# touch_w_scroll.net
KiCad netlist of a schematic drawn in EAGLE
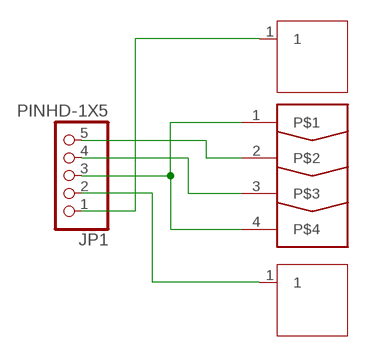
[diagram p0: schematic, sheet 1]

(export (version "E")
  (design (tool "Eeschema 10.0.6"))
  (components
    (comp (ref "JP1")
      (value "PINHD-1X5")
      (footprint "eagle-import:1X05")
      (libsource (lib "eagle-import") (part "PINHD-1X5"))
    )
    (comp (ref "U$1")
      (value "SLIDE_PAD")
      (footprint "eagle-import:SLIDE")
      (libsource (lib "eagle-import") (part "SLIDE_PAD"))
    )
    (comp (ref "U$2")
      (value "12X12_PAD")
      (footprint "eagle-import:12X12_PAD")
      (libsource (lib "eagle-import") (part "12X12_PAD"))
    )
    (comp (ref "U$4")
      (value "12X12_PADLED")
      (footprint "eagle-import:12X12_PAD_LED")
      (libsource (lib "eagle-import") (part "12X12_PADLED"))
    )
  )
  (nets
    (net (code "1") (name "Net-(JP1-Pad1)") (class "Default")
      (node (ref "JP1") (pin "1") (pinfunction "1_1") (pintype "passive"))
      (node (ref "U$2") (pin "1") (pinfunction "1_1") (pintype "bidirectional"))
    )
    (net (code "2") (name "Net-(JP1-Pad2)") (class "Default")
      (node (ref "JP1") (pin "2") (pinfunction "2_2") (pintype "passive"))
      (node (ref "U$4") (pin "1") (pinfunction "1_1") (pintype "bidirectional"))
    )
    (net (code "3") (name "Net-(U$1-P$1)") (class "Default")
      (node (ref "JP1") (pin "3") (pinfunction "3_3") (pintype "passive"))
      (node (ref "U$1") (pin "1") (pinfunction "P$1_1") (pintype "bidirectional"))
      (node (ref "U$1") (pin "4") (pinfunction "P$4_4") (pintype "bidirectional"))
    )
    (net (code "4") (name "Net-(U$1-P$2)") (class "Default")
      (node (ref "JP1") (pin "5") (pinfunction "5_5") (pintype "passive"))
      (node (ref "U$1") (pin "2") (pinfunction "P$2_2") (pintype "bidirectional"))
    )
    (net (code "5") (name "Net-(U$1-P$3)") (class "Default")
      (node (ref "JP1") (pin "4") (pinfunction "4_4") (pintype "passive"))
      (node (ref "U$1") (pin "3") (pinfunction "P$3_3") (pintype "bidirectional"))
    )
  )
)
